# Serial_CAN_Bus_V1_2.net
KiCad netlist of a schematic drawn in EAGLE
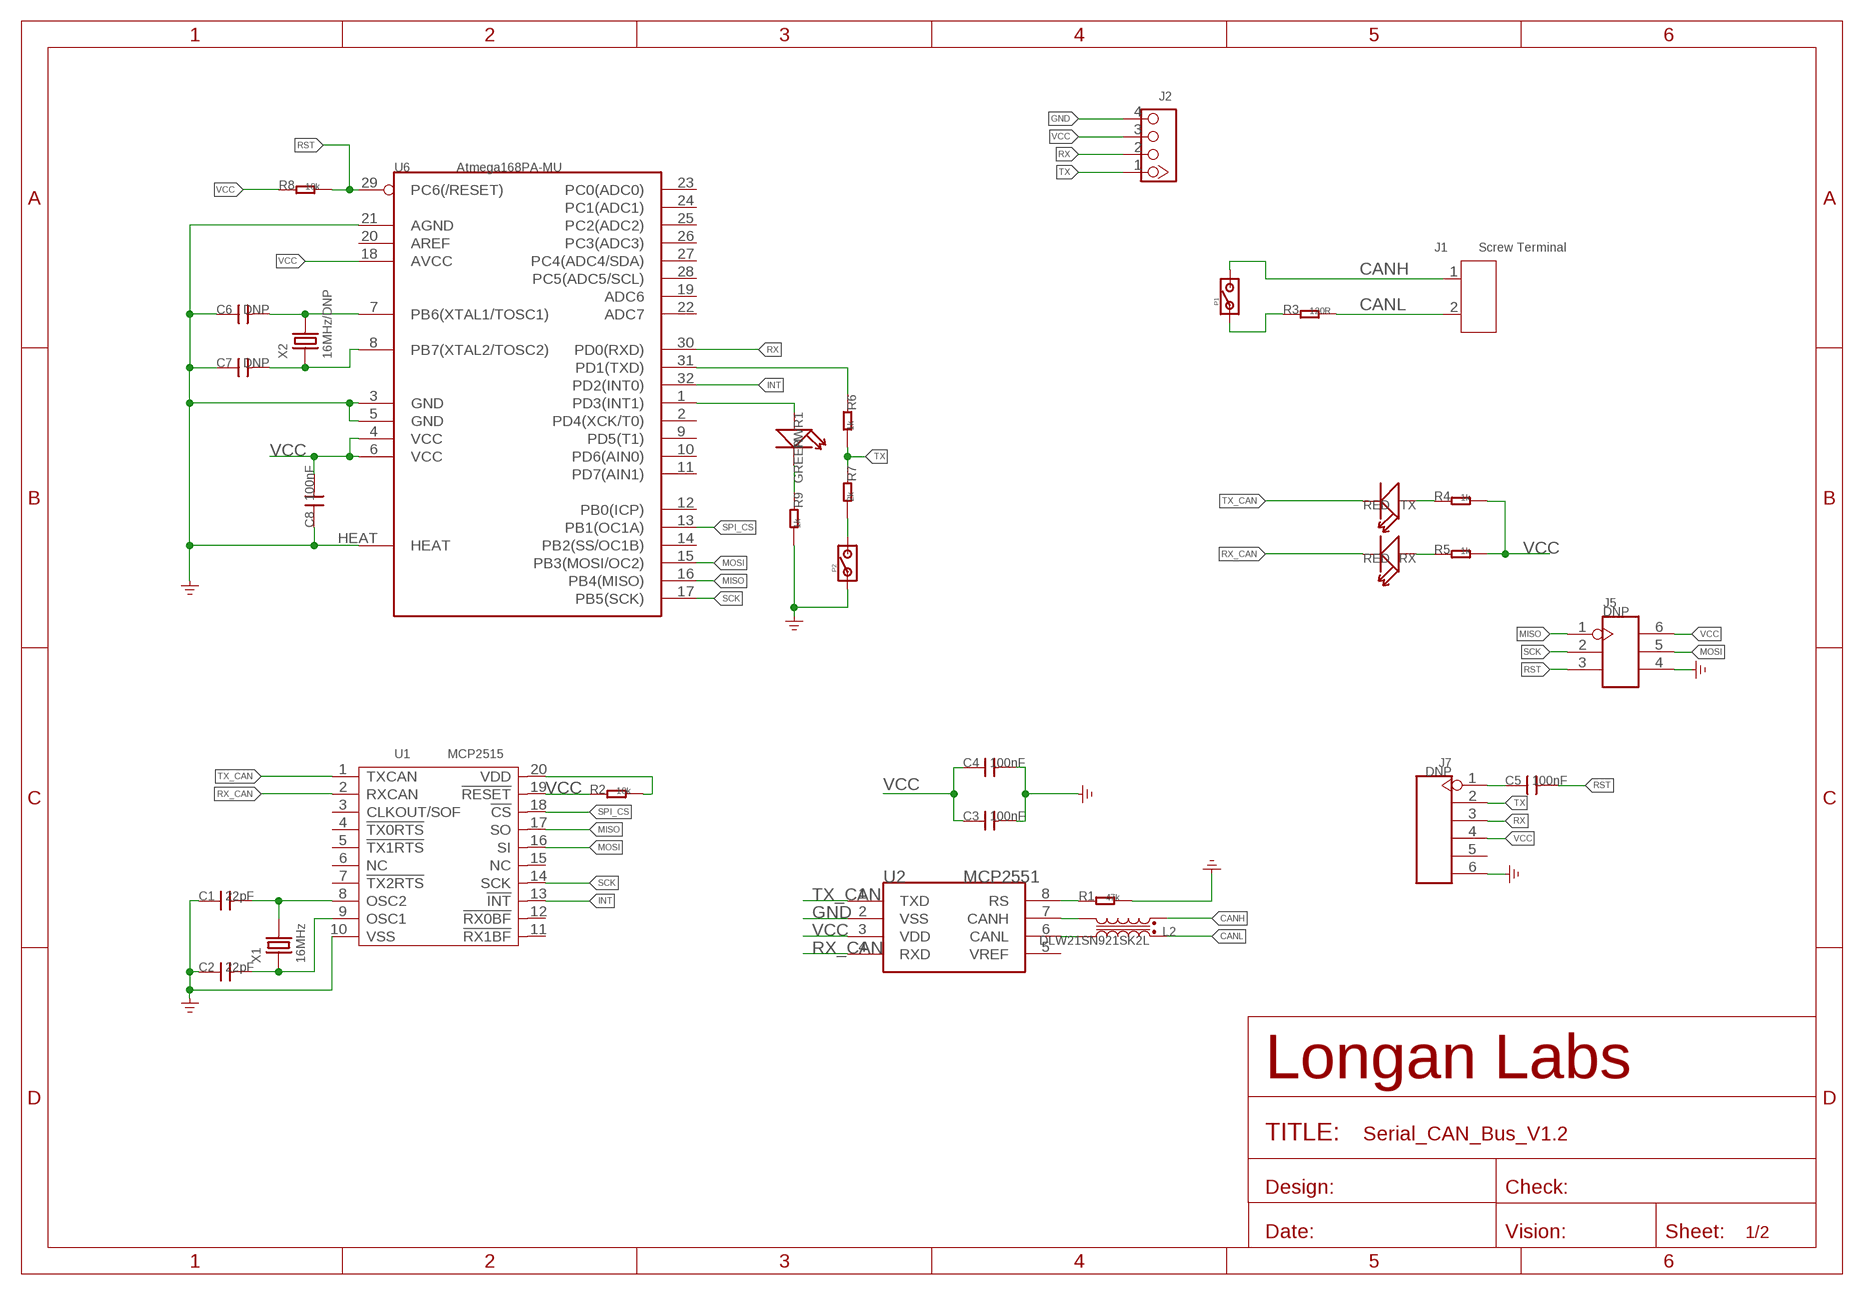
[diagram p0: schematic, sheet 1]

(export (version "E")
  (design (tool "Eeschema 10.0.6"))
  (components
    (comp (ref "C1")
      (value "22pF")
      (footprint "eagle-import:0603")
      (libsource (lib "eagle-import") (part "C-0603"))
    )
    (comp (ref "C2")
      (value "22pF")
      (footprint "eagle-import:0603")
      (libsource (lib "eagle-import") (part "C-0603"))
    )
    (comp (ref "C3")
      (value "100nF")
      (footprint "eagle-import:0603")
      (libsource (lib "eagle-import") (part "C-0603"))
    )
    (comp (ref "C4")
      (value "100nF")
      (footprint "eagle-import:0603")
      (libsource (lib "eagle-import") (part "C-0603"))
    )
    (comp (ref "C5")
      (value "100nF")
      (footprint "eagle-import:0603")
      (libsource (lib "eagle-import") (part "C-0603"))
    )
    (comp (ref "C6")
      (value "DNP")
      (footprint "eagle-import:0603")
      (libsource (lib "eagle-import") (part "C-0603"))
    )
    (comp (ref "C7")
      (value "DNP")
      (footprint "eagle-import:0603")
      (libsource (lib "eagle-import") (part "C-0603"))
    )
    (comp (ref "C8")
      (value "100nF")
      (footprint "eagle-import:0603")
      (libsource (lib "eagle-import") (part "C-0603"))
    )
    (comp (ref "J1")
      (value "Screw Terminal")
      (footprint "eagle-import:2P-3.5")
      (libsource (lib "eagle-import") (part "SCREW-TERMINAL-2P'3.5'"))
    )
    (comp (ref "J2")
      (value "320110033")
      (footprint "eagle-import:HW4-2.0")
      (libsource (lib "eagle-import") (part "GROVE-CONNECTOR-DIP-2.0"))
    )
    (comp (ref "J5")
      (value "DNP")
      (footprint "eagle-import:H2X3-SMD-2.0(1.143)")
      (libsource (lib "eagle-import") (part "HEADER-2X3P-2.0-1.143"))
    )
    (comp (ref "J7")
      (value "DNP")
      (footprint "eagle-import:H6-2.54")
      (libsource (lib "eagle-import") (part "HEADER-6P-55/35MIL"))
    )
    (comp (ref "L2")
      (value "DLW21SN921SK2L")
      (footprint "eagle-import:INT4-0.85-2X1.25X1.2MM")
      (libsource (lib "eagle-import") (part "INDUCTOR-COMMON-MODE-SRF2012-900YA"))
    )
    (comp (ref "P1")
      (value "PAD-JUMPER-2P")
      (footprint "eagle-import:2P-SMD-1.78X1.27")
      (libsource (lib "eagle-import") (part "PAD-JUMPER-2P"))
    )
    (comp (ref "P2")
      (value "PAD-JUMPER-2P")
      (footprint "eagle-import:2P-SMD-1.78X1.27")
      (libsource (lib "eagle-import") (part "PAD-JUMPER-2P"))
    )
    (comp (ref "PWR1")
      (value "GREEN")
      (footprint "eagle-import:LED-0603")
      (libsource (lib "eagle-import") (part "LED'0603'"))
    )
    (comp (ref "R1")
      (value "47k")
      (footprint "eagle-import:0603")
      (libsource (lib "eagle-import") (part "R-0603"))
    )
    (comp (ref "R2")
      (value "10k")
      (footprint "eagle-import:0603")
      (libsource (lib "eagle-import") (part "R-0603"))
    )
    (comp (ref "R3")
      (value "120R")
      (footprint "eagle-import:0603")
      (libsource (lib "eagle-import") (part "R-0603"))
    )
    (comp (ref "R4")
      (value "1k")
      (footprint "eagle-import:0603")
      (libsource (lib "eagle-import") (part "R-0603"))
    )
    (comp (ref "R5")
      (value "1k")
      (footprint "eagle-import:0603")
      (libsource (lib "eagle-import") (part "R-0603"))
    )
    (comp (ref "R6")
      (value "1k")
      (footprint "eagle-import:0603")
      (libsource (lib "eagle-import") (part "R-0603"))
    )
    (comp (ref "R7")
      (value "2k")
      (footprint "eagle-import:0603")
      (libsource (lib "eagle-import") (part "R-0603"))
    )
    (comp (ref "R8")
      (value "10k")
      (footprint "eagle-import:0603")
      (libsource (lib "eagle-import") (part "R-0603"))
    )
    (comp (ref "R9")
      (value "1k")
      (footprint "eagle-import:0603")
      (libsource (lib "eagle-import") (part "R-0603"))
    )
    (comp (ref "RX")
      (value "RED")
      (footprint "eagle-import:LED-0603")
      (libsource (lib "eagle-import") (part "LED'0603'"))
    )
    (comp (ref "TX")
      (value "RED")
      (footprint "eagle-import:LED-0603")
      (libsource (lib "eagle-import") (part "LED'0603'"))
    )
    (comp (ref "U1")
      (value "MCP2515")
      (footprint "eagle-import:TSSOP20-0.65-6.5X4.4MM")
      (libsource (lib "eagle-import") (part "MCP2515'ST'"))
    )
    (comp (ref "U2")
      (value "MCP2551")
      (footprint "eagle-import:SOIC8-6.0")
      (libsource (lib "eagle-import") (part "MCP2551-SOIC8"))
    )
    (comp (ref "U6")
      (value "Atmega168PA-MU")
      (footprint "eagle-import:MLF32X")
      (libsource (lib "eagle-import") (part "MEGA8"))
    )
    (comp (ref "X1")
      (value "16MHz")
      (footprint "eagle-import:X2-SMD-5.0X3.2X1.3MM")
      (libsource (lib "eagle-import") (part "CRYSTAL-2P'5032'"))
    )
    (comp (ref "X2")
      (value "16MHz/DNP")
      (footprint "eagle-import:X2-SMD-5.0X3.2X1.3MM")
      (libsource (lib "eagle-import") (part "CRYSTAL-2P'5032'"))
    )
  )
  (nets
    (net (code "1") (name "CANH") (class "Default")
      (node (ref "J1") (pin "1") (pinfunction "1_1") (pintype "bidirectional"))
      (node (ref "L2") (pin "4") (pinfunction "4_4") (pintype "bidirectional"))
      (node (ref "P1") (pin "2") (pinfunction "2_2") (pintype "bidirectional"))
    )
    (net (code "2") (name "CANL") (class "Default")
      (node (ref "J1") (pin "2") (pinfunction "2_2") (pintype "bidirectional"))
      (node (ref "L2") (pin "1") (pinfunction "1_1") (pintype "bidirectional"))
      (node (ref "R3") (pin "2") (pinfunction "2_2") (pintype "passive"))
    )
    (net (code "3") (name "GND") (class "Default")
      (node (ref "C1") (pin "1") (pinfunction "1_1") (pintype "passive"))
      (node (ref "C2") (pin "1") (pinfunction "1_1") (pintype "passive"))
      (node (ref "C3") (pin "2") (pinfunction "2_2") (pintype "passive"))
      (node (ref "C4") (pin "2") (pinfunction "2_2") (pintype "passive"))
      (node (ref "C6") (pin "1") (pinfunction "1_1") (pintype "passive"))
      (node (ref "C7") (pin "1") (pinfunction "1_1") (pintype "passive"))
      (node (ref "C8") (pin "1") (pinfunction "1_1") (pintype "passive"))
      (node (ref "J2") (pin "4") (pinfunction "4_4") (pintype "bidirectional"))
      (node (ref "J5") (pin "4") (pinfunction "4_4") (pintype "bidirectional"))
      (node (ref "J7") (pin "6") (pinfunction "6_6") (pintype "bidirectional"))
      (node (ref "P2") (pin "1") (pinfunction "1_1") (pintype "bidirectional"))
      (node (ref "R1") (pin "2") (pinfunction "2_2") (pintype "passive"))
      (node (ref "R9") (pin "2") (pinfunction "2_2") (pintype "passive"))
      (node (ref "U1") (pin "10") (pinfunction "VSS_10") (pintype "bidirectional"))
      (node (ref "U2") (pin "2") (pinfunction "VSS_2") (pintype "bidirectional"))
      (node (ref "U6") (pin "21") (pinfunction "AGND_21") (pintype "bidirectional"))
      (node (ref "U6") (pin "3") (pinfunction "GND_3") (pintype "bidirectional"))
      (node (ref "U6") (pin "5") (pinfunction "GND_5") (pintype "bidirectional"))
      (node (ref "U6") (pin "HEAT") (pinfunction "HEAT_HEAT") (pintype "bidirectional"))
    )
    (net (code "4") (name "INT") (class "Default")
      (node (ref "U1") (pin "13") (pinfunction "~{INT}_13") (pintype "bidirectional"))
      (node (ref "U6") (pin "32") (pinfunction "PD2(INT0)_32") (pintype "bidirectional"))
    )
    (net (code "5") (name "MISO") (class "Default")
      (node (ref "J5") (pin "1") (pinfunction "1_1") (pintype "bidirectional"))
      (node (ref "U1") (pin "17") (pinfunction "SO_17") (pintype "bidirectional"))
      (node (ref "U6") (pin "16") (pinfunction "PB4(MISO)_16") (pintype "bidirectional"))
    )
    (net (code "6") (name "MOSI") (class "Default")
      (node (ref "J5") (pin "5") (pinfunction "5_5") (pintype "bidirectional"))
      (node (ref "U1") (pin "16") (pinfunction "SI_16") (pintype "bidirectional"))
      (node (ref "U6") (pin "15") (pinfunction "PB3(MOSI/OC2)_15") (pintype "bidirectional"))
    )
    (net (code "7") (name "Net-(C5-Pad1)") (class "Default")
      (node (ref "C5") (pin "1") (pinfunction "1_1") (pintype "passive"))
      (node (ref "J7") (pin "1") (pinfunction "1_1") (pintype "bidirectional"))
    )
    (net (code "8") (name "Net-(P1-Pad1)") (class "Default")
      (node (ref "P1") (pin "1") (pinfunction "1_1") (pintype "bidirectional"))
      (node (ref "R3") (pin "1") (pinfunction "1_1") (pintype "passive"))
    )
    (net (code "9") (name "Net-(P2-Pad2)") (class "Default")
      (node (ref "P2") (pin "2") (pinfunction "2_2") (pintype "bidirectional"))
      (node (ref "R7") (pin "2") (pinfunction "2_2") (pintype "passive"))
    )
    (net (code "10") (name "Net-(PWR1-Pad-)") (class "Default")
      (node (ref "PWR1") (pin "-") (pinfunction "-_-") (pintype "passive"))
      (node (ref "R9") (pin "1") (pinfunction "1_1") (pintype "passive"))
    )
    (net (code "11") (name "Net-(R4-Pad1)") (class "Default")
      (node (ref "R4") (pin "1") (pinfunction "1_1") (pintype "passive"))
      (node (ref "TX") (pin "+") (pinfunction "+_+") (pintype "passive"))
    )
    (net (code "12") (name "Net-(R5-Pad1)") (class "Default")
      (node (ref "R5") (pin "1") (pinfunction "1_1") (pintype "passive"))
      (node (ref "RX") (pin "+") (pinfunction "+_+") (pintype "passive"))
    )
    (net (code "13") (name "Net-(U1-OSC1)") (class "Default")
      (node (ref "C2") (pin "2") (pinfunction "2_2") (pintype "passive"))
      (node (ref "U1") (pin "9") (pinfunction "OSC1_9") (pintype "bidirectional"))
      (node (ref "X1") (pin "1") (pinfunction "1_1") (pintype "passive"))
    )
    (net (code "14") (name "Net-(U1-OSC2)") (class "Default")
      (node (ref "C1") (pin "2") (pinfunction "2_2") (pintype "passive"))
      (node (ref "U1") (pin "8") (pinfunction "OSC2_8") (pintype "bidirectional"))
      (node (ref "X1") (pin "2") (pinfunction "2_2") (pintype "passive"))
    )
    (net (code "15") (name "Net-(U1-~{RESET})") (class "Default")
      (node (ref "R2") (pin "1") (pinfunction "1_1") (pintype "passive"))
      (node (ref "U1") (pin "19") (pinfunction "~{RESET}_19") (pintype "bidirectional"))
    )
    (net (code "16") (name "Net-(U2-CANH)") (class "Default")
      (node (ref "L2") (pin "3") (pinfunction "3_3") (pintype "bidirectional"))
      (node (ref "U2") (pin "7") (pinfunction "CANH_7") (pintype "bidirectional"))
    )
    (net (code "17") (name "Net-(U2-CANL)") (class "Default")
      (node (ref "L2") (pin "2") (pinfunction "2_2") (pintype "bidirectional"))
      (node (ref "U2") (pin "6") (pinfunction "CANL_6") (pintype "bidirectional"))
    )
    (net (code "18") (name "Net-(U2-RS)") (class "Default")
      (node (ref "R1") (pin "1") (pinfunction "1_1") (pintype "passive"))
      (node (ref "U2") (pin "8") (pinfunction "RS_8") (pintype "bidirectional"))
    )
    (net (code "19") (name "Net-(U6-PB6(XTAL1{slash}TOSC1))") (class "Default")
      (node (ref "C6") (pin "2") (pinfunction "2_2") (pintype "passive"))
      (node (ref "U6") (pin "7") (pinfunction "PB6(XTAL1/TOSC1)_7") (pintype "bidirectional"))
      (node (ref "X2") (pin "2") (pinfunction "2_2") (pintype "passive"))
    )
    (net (code "20") (name "Net-(U6-PB7(XTAL2{slash}TOSC2))") (class "Default")
      (node (ref "C7") (pin "2") (pinfunction "2_2") (pintype "passive"))
      (node (ref "U6") (pin "8") (pinfunction "PB7(XTAL2/TOSC2)_8") (pintype "bidirectional"))
      (node (ref "X2") (pin "1") (pinfunction "1_1") (pintype "passive"))
    )
    (net (code "21") (name "Net-(U6-PD1(TXD))") (class "Default")
      (node (ref "R6") (pin "1") (pinfunction "1_1") (pintype "passive"))
      (node (ref "U6") (pin "31") (pinfunction "PD1(TXD)_31") (pintype "bidirectional"))
    )
    (net (code "22") (name "Net-(U6-PD3(INT1))") (class "Default")
      (node (ref "PWR1") (pin "+") (pinfunction "+_+") (pintype "passive"))
      (node (ref "U6") (pin "1") (pinfunction "PD3(INT1)_1") (pintype "bidirectional"))
    )
    (net (code "23") (name "RST") (class "Default")
      (node (ref "C5") (pin "2") (pinfunction "2_2") (pintype "passive"))
      (node (ref "J5") (pin "3") (pinfunction "3_3") (pintype "bidirectional"))
      (node (ref "R8") (pin "2") (pinfunction "2_2") (pintype "passive"))
      (node (ref "U6") (pin "29") (pinfunction "PC6(/RESET)_29") (pintype "bidirectional"))
    )
    (net (code "24") (name "RX") (class "Default")
      (node (ref "J2") (pin "2") (pinfunction "2_2") (pintype "bidirectional"))
      (node (ref "J7") (pin "3") (pinfunction "3_3") (pintype "bidirectional"))
      (node (ref "U6") (pin "30") (pinfunction "PD0(RXD)_30") (pintype "bidirectional"))
    )
    (net (code "25") (name "RX_CAN") (class "Default")
      (node (ref "RX") (pin "-") (pinfunction "-_-") (pintype "passive"))
      (node (ref "U1") (pin "2") (pinfunction "RXCAN_2") (pintype "bidirectional"))
      (node (ref "U2") (pin "4") (pinfunction "RXD_4") (pintype "bidirectional"))
    )
    (net (code "26") (name "SCK") (class "Default")
      (node (ref "J5") (pin "2") (pinfunction "2_2") (pintype "bidirectional"))
      (node (ref "U1") (pin "14") (pinfunction "SCK_14") (pintype "bidirectional"))
      (node (ref "U6") (pin "17") (pinfunction "PB5(SCK)_17") (pintype "bidirectional"))
    )
    (net (code "27") (name "SPI_CS") (class "Default")
      (node (ref "U1") (pin "18") (pinfunction "~{CS}_18") (pintype "bidirectional"))
      (node (ref "U6") (pin "13") (pinfunction "PB1(OC1A)_13") (pintype "bidirectional"))
    )
    (net (code "28") (name "TX") (class "Default")
      (node (ref "J2") (pin "1") (pinfunction "1_1") (pintype "bidirectional"))
      (node (ref "J7") (pin "2") (pinfunction "2_2") (pintype "bidirectional"))
      (node (ref "R6") (pin "2") (pinfunction "2_2") (pintype "passive"))
      (node (ref "R7") (pin "1") (pinfunction "1_1") (pintype "passive"))
    )
    (net (code "29") (name "TX_CAN") (class "Default")
      (node (ref "TX") (pin "-") (pinfunction "-_-") (pintype "passive"))
      (node (ref "U1") (pin "1") (pinfunction "TXCAN_1") (pintype "bidirectional"))
      (node (ref "U2") (pin "1") (pinfunction "TXD_1") (pintype "bidirectional"))
    )
    (net (code "30") (name "VCC") (class "Default")
      (node (ref "C3") (pin "1") (pinfunction "1_1") (pintype "passive"))
      (node (ref "C4") (pin "1") (pinfunction "1_1") (pintype "passive"))
      (node (ref "C8") (pin "2") (pinfunction "2_2") (pintype "passive"))
      (node (ref "J2") (pin "3") (pinfunction "3_3") (pintype "bidirectional"))
      (node (ref "J5") (pin "6") (pinfunction "6_6") (pintype "bidirectional"))
      (node (ref "J7") (pin "4") (pinfunction "4_4") (pintype "bidirectional"))
      (node (ref "R2") (pin "2") (pinfunction "2_2") (pintype "passive"))
      (node (ref "R4") (pin "2") (pinfunction "2_2") (pintype "passive"))
      (node (ref "R5") (pin "2") (pinfunction "2_2") (pintype "passive"))
      (node (ref "R8") (pin "1") (pinfunction "1_1") (pintype "passive"))
      (node (ref "U1") (pin "20") (pinfunction "VDD_20") (pintype "bidirectional"))
      (node (ref "U2") (pin "3") (pinfunction "VDD_3") (pintype "bidirectional"))
      (node (ref "U6") (pin "18") (pinfunction "AVCC_18") (pintype "bidirectional"))
      (node (ref "U6") (pin "4") (pinfunction "VCC_4") (pintype "bidirectional"))
      (node (ref "U6") (pin "6") (pinfunction "VCC_6") (pintype "bidirectional"))
    )
    (net (code "31") (name "unconnected-(J7-Pad5)") (class "Default")
      (node (ref "J7") (pin "5") (pinfunction "5_5") (pintype "bidirectional"))
    )
    (net (code "32") (name "unconnected-(U1-CLKOUT{slash}SOF-Pad3)") (class "Default")
      (node (ref "U1") (pin "3") (pinfunction "CLKOUT/SOF_3") (pintype "bidirectional"))
    )
    (net (code "33") (name "unconnected-(U1-NC-Pad6)") (class "Default")
      (node (ref "U1") (pin "6") (pinfunction "NC_6") (pintype "bidirectional"))
    )
    (net (code "34") (name "unconnected-(U1-NC-Pad15)") (class "Default")
      (node (ref "U1") (pin "15") (pinfunction "NC_15") (pintype "bidirectional"))
    )
    (net (code "35") (name "unconnected-(U1-~{RX0BF}-Pad12)") (class "Default")
      (node (ref "U1") (pin "12") (pinfunction "~{RX0BF}_12") (pintype "bidirectional"))
    )
    (net (code "36") (name "unconnected-(U1-~{RX1BF}-Pad11)") (class "Default")
      (node (ref "U1") (pin "11") (pinfunction "~{RX1BF}_11") (pintype "bidirectional"))
    )
    (net (code "37") (name "unconnected-(U1-~{TX0RTS}-Pad4)") (class "Default")
      (node (ref "U1") (pin "4") (pinfunction "~{TX0RTS}_4") (pintype "bidirectional"))
    )
    (net (code "38") (name "unconnected-(U1-~{TX1RTS}-Pad5)") (class "Default")
      (node (ref "U1") (pin "5") (pinfunction "~{TX1RTS}_5") (pintype "bidirectional"))
    )
    (net (code "39") (name "unconnected-(U1-~{TX2RTS}-Pad7)") (class "Default")
      (node (ref "U1") (pin "7") (pinfunction "~{TX2RTS}_7") (pintype "bidirectional"))
    )
    (net (code "40") (name "unconnected-(U2-VREF-Pad5)") (class "Default")
      (node (ref "U2") (pin "5") (pinfunction "VREF_5") (pintype "bidirectional"))
    )
    (net (code "41") (name "unconnected-(U6-ADC6-Pad19)") (class "Default")
      (node (ref "U6") (pin "19") (pinfunction "ADC6_19") (pintype "bidirectional"))
    )
    (net (code "42") (name "unconnected-(U6-ADC7-Pad22)") (class "Default")
      (node (ref "U6") (pin "22") (pinfunction "ADC7_22") (pintype "bidirectional"))
    )
    (net (code "43") (name "unconnected-(U6-AREF-Pad20)") (class "Default")
      (node (ref "U6") (pin "20") (pinfunction "AREF_20") (pintype "bidirectional"))
    )
    (net (code "44") (name "unconnected-(U6-PB0(ICP)-Pad12)") (class "Default")
      (node (ref "U6") (pin "12") (pinfunction "PB0(ICP)_12") (pintype "bidirectional"))
    )
    (net (code "45") (name "unconnected-(U6-PB2(SS{slash}OC1B)-Pad14)") (class "Default")
      (node (ref "U6") (pin "14") (pinfunction "PB2(SS/OC1B)_14") (pintype "bidirectional"))
    )
    (net (code "46") (name "unconnected-(U6-PC0(ADC0)-Pad23)") (class "Default")
      (node (ref "U6") (pin "23") (pinfunction "PC0(ADC0)_23") (pintype "bidirectional"))
    )
    (net (code "47") (name "unconnected-(U6-PC1(ADC1)-Pad24)") (class "Default")
      (node (ref "U6") (pin "24") (pinfunction "PC1(ADC1)_24") (pintype "bidirectional"))
    )
    (net (code "48") (name "unconnected-(U6-PC2(ADC2)-Pad25)") (class "Default")
      (node (ref "U6") (pin "25") (pinfunction "PC2(ADC2)_25") (pintype "bidirectional"))
    )
    (net (code "49") (name "unconnected-(U6-PC3(ADC3)-Pad26)") (class "Default")
      (node (ref "U6") (pin "26") (pinfunction "PC3(ADC3)_26") (pintype "bidirectional"))
    )
    (net (code "50") (name "unconnected-(U6-PC4(ADC4{slash}SDA)-Pad27)") (class "Default")
      (node (ref "U6") (pin "27") (pinfunction "PC4(ADC4/SDA)_27") (pintype "bidirectional"))
    )
    (net (code "51") (name "unconnected-(U6-PC5(ADC5{slash}SCL)-Pad28)") (class "Default")
      (node (ref "U6") (pin "28") (pinfunction "PC5(ADC5/SCL)_28") (pintype "bidirectional"))
    )
    (net (code "52") (name "unconnected-(U6-PD4(XCK{slash}T0)-Pad2)") (class "Default")
      (node (ref "U6") (pin "2") (pinfunction "PD4(XCK/T0)_2") (pintype "bidirectional"))
    )
    (net (code "53") (name "unconnected-(U6-PD5(T1)-Pad9)") (class "Default")
      (node (ref "U6") (pin "9") (pinfunction "PD5(T1)_9") (pintype "bidirectional"))
    )
    (net (code "54") (name "unconnected-(U6-PD6(AIN0)-Pad10)") (class "Default")
      (node (ref "U6") (pin "10") (pinfunction "PD6(AIN0)_10") (pintype "bidirectional"))
    )
    (net (code "55") (name "unconnected-(U6-PD7(AIN1)-Pad11)") (class "Default")
      (node (ref "U6") (pin "11") (pinfunction "PD7(AIN1)_11") (pintype "bidirectional"))
    )
  )
)
